# ROM_1_0.net
KiCad netlist of a schematic drawn in EAGLE
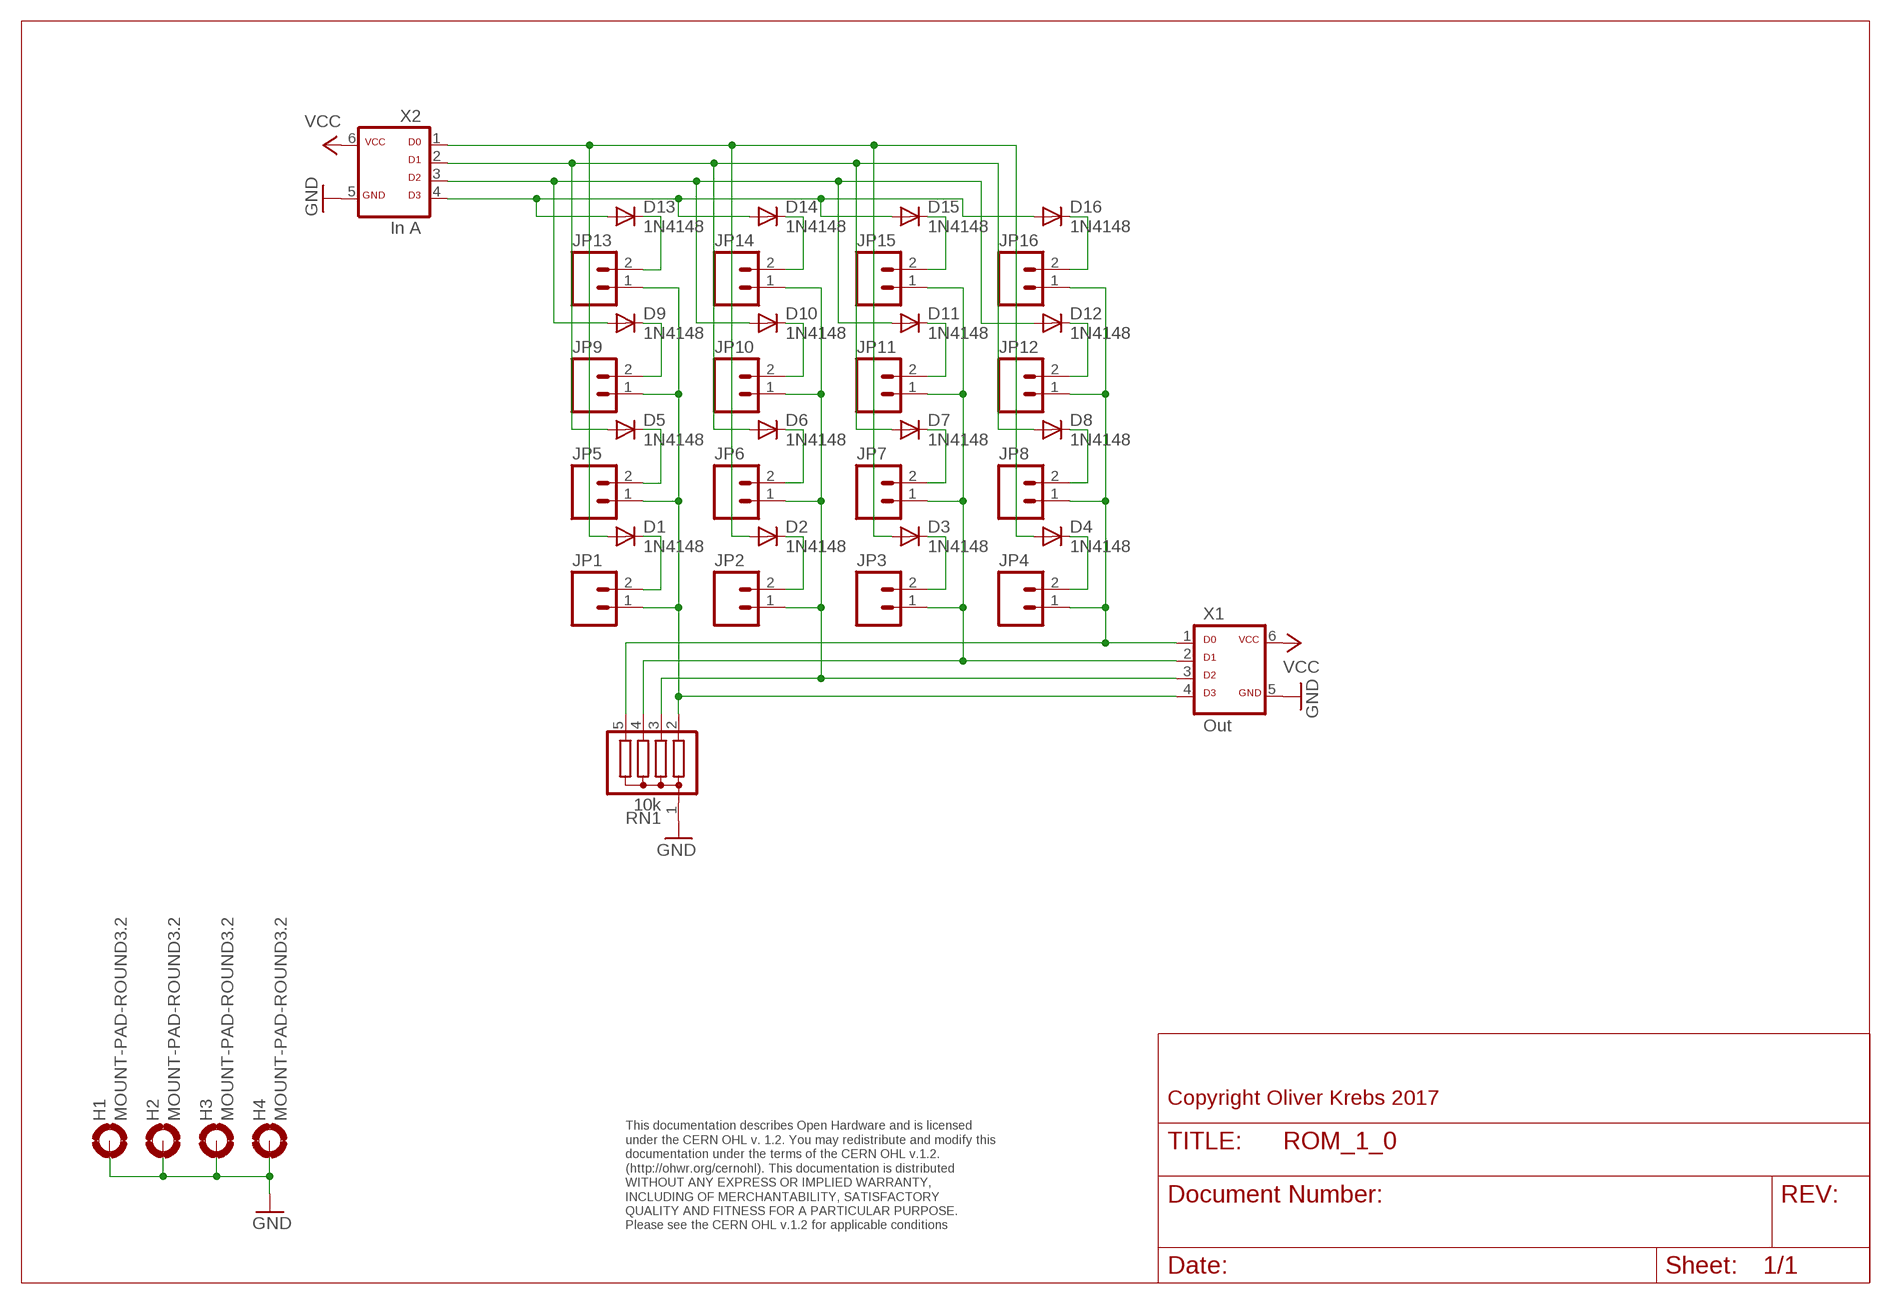
[diagram p0: schematic, sheet 1]

(export (version "E")
  (design (tool "Eeschema 10.0.6"))
  (components
    (comp (ref "D1")
      (value "1N4148")
      (footprint "eagle-import:DO35-7")
      (libsource (lib "eagle-import") (part "1N4148DO35-7"))
    )
    (comp (ref "D2")
      (value "1N4148")
      (footprint "eagle-import:DO35-7")
      (libsource (lib "eagle-import") (part "1N4148DO35-7"))
    )
    (comp (ref "D3")
      (value "1N4148")
      (footprint "eagle-import:DO35-7")
      (libsource (lib "eagle-import") (part "1N4148DO35-7"))
    )
    (comp (ref "D4")
      (value "1N4148")
      (footprint "eagle-import:DO35-7")
      (libsource (lib "eagle-import") (part "1N4148DO35-7"))
    )
    (comp (ref "D5")
      (value "1N4148")
      (footprint "eagle-import:DO35-7")
      (libsource (lib "eagle-import") (part "1N4148DO35-7"))
    )
    (comp (ref "D6")
      (value "1N4148")
      (footprint "eagle-import:DO35-7")
      (libsource (lib "eagle-import") (part "1N4148DO35-7"))
    )
    (comp (ref "D7")
      (value "1N4148")
      (footprint "eagle-import:DO35-7")
      (libsource (lib "eagle-import") (part "1N4148DO35-7"))
    )
    (comp (ref "D8")
      (value "1N4148")
      (footprint "eagle-import:DO35-7")
      (libsource (lib "eagle-import") (part "1N4148DO35-7"))
    )
    (comp (ref "D9")
      (value "1N4148")
      (footprint "eagle-import:DO35-7")
      (libsource (lib "eagle-import") (part "1N4148DO35-7"))
    )
    (comp (ref "D10")
      (value "1N4148")
      (footprint "eagle-import:DO35-7")
      (libsource (lib "eagle-import") (part "1N4148DO35-7"))
    )
    (comp (ref "D11")
      (value "1N4148")
      (footprint "eagle-import:DO35-7")
      (libsource (lib "eagle-import") (part "1N4148DO35-7"))
    )
    (comp (ref "D12")
      (value "1N4148")
      (footprint "eagle-import:DO35-7")
      (libsource (lib "eagle-import") (part "1N4148DO35-7"))
    )
    (comp (ref "D13")
      (value "1N4148")
      (footprint "eagle-import:DO35-7")
      (libsource (lib "eagle-import") (part "1N4148DO35-7"))
    )
    (comp (ref "D14")
      (value "1N4148")
      (footprint "eagle-import:DO35-7")
      (libsource (lib "eagle-import") (part "1N4148DO35-7"))
    )
    (comp (ref "D15")
      (value "1N4148")
      (footprint "eagle-import:DO35-7")
      (libsource (lib "eagle-import") (part "1N4148DO35-7"))
    )
    (comp (ref "D16")
      (value "1N4148")
      (footprint "eagle-import:DO35-7")
      (libsource (lib "eagle-import") (part "1N4148DO35-7"))
    )
    (comp (ref "H1")
      (value "MOUNT-PAD-ROUND3.2")
      (footprint "eagle-import:3,2-PAD")
      (libsource (lib "eagle-import") (part "MOUNT-PAD-ROUND3.2"))
    )
    (comp (ref "H2")
      (value "MOUNT-PAD-ROUND3.2")
      (footprint "eagle-import:3,2-PAD")
      (libsource (lib "eagle-import") (part "MOUNT-PAD-ROUND3.2"))
    )
    (comp (ref "H3")
      (value "MOUNT-PAD-ROUND3.2")
      (footprint "eagle-import:3,2-PAD")
      (libsource (lib "eagle-import") (part "MOUNT-PAD-ROUND3.2"))
    )
    (comp (ref "H4")
      (value "MOUNT-PAD-ROUND3.2")
      (footprint "eagle-import:3,2-PAD")
      (libsource (lib "eagle-import") (part "MOUNT-PAD-ROUND3.2"))
    )
    (comp (ref "JP1")
      (value "M02PTH")
      (footprint "eagle-import:1X02")
      (libsource (lib "eagle-import") (part "M02PTH"))
    )
    (comp (ref "JP2")
      (value "M02PTH")
      (footprint "eagle-import:1X02")
      (libsource (lib "eagle-import") (part "M02PTH"))
    )
    (comp (ref "JP3")
      (value "M02PTH")
      (footprint "eagle-import:1X02")
      (libsource (lib "eagle-import") (part "M02PTH"))
    )
    (comp (ref "JP4")
      (value "M02PTH")
      (footprint "eagle-import:1X02")
      (libsource (lib "eagle-import") (part "M02PTH"))
    )
    (comp (ref "JP5")
      (value "M02PTH")
      (footprint "eagle-import:1X02")
      (libsource (lib "eagle-import") (part "M02PTH"))
    )
    (comp (ref "JP6")
      (value "M02PTH")
      (footprint "eagle-import:1X02")
      (libsource (lib "eagle-import") (part "M02PTH"))
    )
    (comp (ref "JP7")
      (value "M02PTH")
      (footprint "eagle-import:1X02")
      (libsource (lib "eagle-import") (part "M02PTH"))
    )
    (comp (ref "JP8")
      (value "M02PTH")
      (footprint "eagle-import:1X02")
      (libsource (lib "eagle-import") (part "M02PTH"))
    )
    (comp (ref "JP9")
      (value "M02PTH")
      (footprint "eagle-import:1X02")
      (libsource (lib "eagle-import") (part "M02PTH"))
    )
    (comp (ref "JP10")
      (value "M02PTH")
      (footprint "eagle-import:1X02")
      (libsource (lib "eagle-import") (part "M02PTH"))
    )
    (comp (ref "JP11")
      (value "M02PTH")
      (footprint "eagle-import:1X02")
      (libsource (lib "eagle-import") (part "M02PTH"))
    )
    (comp (ref "JP12")
      (value "M02PTH")
      (footprint "eagle-import:1X02")
      (libsource (lib "eagle-import") (part "M02PTH"))
    )
    (comp (ref "JP13")
      (value "M02PTH")
      (footprint "eagle-import:1X02")
      (libsource (lib "eagle-import") (part "M02PTH"))
    )
    (comp (ref "JP14")
      (value "M02PTH")
      (footprint "eagle-import:1X02")
      (libsource (lib "eagle-import") (part "M02PTH"))
    )
    (comp (ref "JP15")
      (value "M02PTH")
      (footprint "eagle-import:1X02")
      (libsource (lib "eagle-import") (part "M02PTH"))
    )
    (comp (ref "JP16")
      (value "M02PTH")
      (footprint "eagle-import:1X02")
      (libsource (lib "eagle-import") (part "M02PTH"))
    )
    (comp (ref "RN1")
      (value "10k")
      (footprint "eagle-import:SIL5")
      (libsource (lib "eagle-import") (part "G04R"))
    )
    (comp (ref "X1")
      (value "Out")
      (footprint "eagle-import:ML-6")
      (libsource (lib "eagle-import") (part "ML6D"))
    )
    (comp (ref "X2")
      (value "In A")
      (footprint "eagle-import:ML-6")
      (libsource (lib "eagle-import") (part "ML6D"))
    )
  )
  (nets
    (net (code "1") (name "GND") (class "Default")
      (node (ref "H1") (pin "B3,2") (pinfunction "MOUNT_B3,2") (pintype "passive"))
      (node (ref "H2") (pin "B3,2") (pinfunction "MOUNT_B3,2") (pintype "passive"))
      (node (ref "H3") (pin "B3,2") (pinfunction "MOUNT_B3,2") (pintype "passive"))
      (node (ref "H4") (pin "B3,2") (pinfunction "MOUNT_B3,2") (pintype "passive"))
      (node (ref "RN1") (pin "1") (pinfunction "1_1") (pintype "passive"))
      (node (ref "X1") (pin "5") (pinfunction "5_5") (pintype "passive"))
      (node (ref "X2") (pin "5") (pinfunction "5_5") (pintype "passive"))
    )
    (net (code "2") (name "Net-(D1-PadA)") (class "Default")
      (node (ref "D1") (pin "A") (pinfunction "A_A") (pintype "passive"))
      (node (ref "D2") (pin "A") (pinfunction "A_A") (pintype "passive"))
      (node (ref "D3") (pin "A") (pinfunction "A_A") (pintype "passive"))
      (node (ref "D4") (pin "A") (pinfunction "A_A") (pintype "passive"))
      (node (ref "X2") (pin "1") (pinfunction "1_1") (pintype "passive"))
    )
    (net (code "3") (name "Net-(D1-PadC)") (class "Default")
      (node (ref "D1") (pin "C") (pinfunction "C_C") (pintype "passive"))
      (node (ref "JP1") (pin "2") (pinfunction "2_2") (pintype "passive"))
    )
    (net (code "4") (name "Net-(D2-PadC)") (class "Default")
      (node (ref "D2") (pin "C") (pinfunction "C_C") (pintype "passive"))
      (node (ref "JP2") (pin "2") (pinfunction "2_2") (pintype "passive"))
    )
    (net (code "5") (name "Net-(D3-PadC)") (class "Default")
      (node (ref "D3") (pin "C") (pinfunction "C_C") (pintype "passive"))
      (node (ref "JP3") (pin "2") (pinfunction "2_2") (pintype "passive"))
    )
    (net (code "6") (name "Net-(D4-PadC)") (class "Default")
      (node (ref "D4") (pin "C") (pinfunction "C_C") (pintype "passive"))
      (node (ref "JP4") (pin "2") (pinfunction "2_2") (pintype "passive"))
    )
    (net (code "7") (name "Net-(D5-PadA)") (class "Default")
      (node (ref "D5") (pin "A") (pinfunction "A_A") (pintype "passive"))
      (node (ref "D6") (pin "A") (pinfunction "A_A") (pintype "passive"))
      (node (ref "D7") (pin "A") (pinfunction "A_A") (pintype "passive"))
      (node (ref "D8") (pin "A") (pinfunction "A_A") (pintype "passive"))
      (node (ref "X2") (pin "2") (pinfunction "2_2") (pintype "passive"))
    )
    (net (code "8") (name "Net-(D5-PadC)") (class "Default")
      (node (ref "D5") (pin "C") (pinfunction "C_C") (pintype "passive"))
      (node (ref "JP5") (pin "2") (pinfunction "2_2") (pintype "passive"))
    )
    (net (code "9") (name "Net-(D6-PadC)") (class "Default")
      (node (ref "D6") (pin "C") (pinfunction "C_C") (pintype "passive"))
      (node (ref "JP6") (pin "2") (pinfunction "2_2") (pintype "passive"))
    )
    (net (code "10") (name "Net-(D7-PadC)") (class "Default")
      (node (ref "D7") (pin "C") (pinfunction "C_C") (pintype "passive"))
      (node (ref "JP7") (pin "2") (pinfunction "2_2") (pintype "passive"))
    )
    (net (code "11") (name "Net-(D8-PadC)") (class "Default")
      (node (ref "D8") (pin "C") (pinfunction "C_C") (pintype "passive"))
      (node (ref "JP8") (pin "2") (pinfunction "2_2") (pintype "passive"))
    )
    (net (code "12") (name "Net-(D9-PadC)") (class "Default")
      (node (ref "D9") (pin "C") (pinfunction "C_C") (pintype "passive"))
      (node (ref "JP9") (pin "2") (pinfunction "2_2") (pintype "passive"))
    )
    (net (code "13") (name "Net-(D10-PadA)") (class "Default")
      (node (ref "D10") (pin "A") (pinfunction "A_A") (pintype "passive"))
      (node (ref "D11") (pin "A") (pinfunction "A_A") (pintype "passive"))
      (node (ref "D12") (pin "A") (pinfunction "A_A") (pintype "passive"))
      (node (ref "D9") (pin "A") (pinfunction "A_A") (pintype "passive"))
      (node (ref "X2") (pin "3") (pinfunction "3_3") (pintype "passive"))
    )
    (net (code "14") (name "Net-(D10-PadC)") (class "Default")
      (node (ref "D10") (pin "C") (pinfunction "C_C") (pintype "passive"))
      (node (ref "JP10") (pin "2") (pinfunction "2_2") (pintype "passive"))
    )
    (net (code "15") (name "Net-(D11-PadC)") (class "Default")
      (node (ref "D11") (pin "C") (pinfunction "C_C") (pintype "passive"))
      (node (ref "JP11") (pin "2") (pinfunction "2_2") (pintype "passive"))
    )
    (net (code "16") (name "Net-(D12-PadC)") (class "Default")
      (node (ref "D12") (pin "C") (pinfunction "C_C") (pintype "passive"))
      (node (ref "JP12") (pin "2") (pinfunction "2_2") (pintype "passive"))
    )
    (net (code "17") (name "Net-(D13-PadA)") (class "Default")
      (node (ref "D13") (pin "A") (pinfunction "A_A") (pintype "passive"))
      (node (ref "D14") (pin "A") (pinfunction "A_A") (pintype "passive"))
      (node (ref "D15") (pin "A") (pinfunction "A_A") (pintype "passive"))
      (node (ref "D16") (pin "A") (pinfunction "A_A") (pintype "passive"))
      (node (ref "X2") (pin "4") (pinfunction "4_4") (pintype "passive"))
    )
    (net (code "18") (name "Net-(D13-PadC)") (class "Default")
      (node (ref "D13") (pin "C") (pinfunction "C_C") (pintype "passive"))
      (node (ref "JP13") (pin "2") (pinfunction "2_2") (pintype "passive"))
    )
    (net (code "19") (name "Net-(D14-PadC)") (class "Default")
      (node (ref "D14") (pin "C") (pinfunction "C_C") (pintype "passive"))
      (node (ref "JP14") (pin "2") (pinfunction "2_2") (pintype "passive"))
    )
    (net (code "20") (name "Net-(D15-PadC)") (class "Default")
      (node (ref "D15") (pin "C") (pinfunction "C_C") (pintype "passive"))
      (node (ref "JP15") (pin "2") (pinfunction "2_2") (pintype "passive"))
    )
    (net (code "21") (name "Net-(D16-PadC)") (class "Default")
      (node (ref "D16") (pin "C") (pinfunction "C_C") (pintype "passive"))
      (node (ref "JP16") (pin "2") (pinfunction "2_2") (pintype "passive"))
    )
    (net (code "22") (name "Net-(JP1-Pad1)") (class "Default")
      (node (ref "JP1") (pin "1") (pinfunction "1_1") (pintype "passive"))
      (node (ref "JP13") (pin "1") (pinfunction "1_1") (pintype "passive"))
      (node (ref "JP5") (pin "1") (pinfunction "1_1") (pintype "passive"))
      (node (ref "JP9") (pin "1") (pinfunction "1_1") (pintype "passive"))
      (node (ref "RN1") (pin "2") (pinfunction "2_2") (pintype "passive"))
      (node (ref "X1") (pin "4") (pinfunction "4_4") (pintype "passive"))
    )
    (net (code "23") (name "Net-(JP10-Pad1)") (class "Default")
      (node (ref "JP10") (pin "1") (pinfunction "1_1") (pintype "passive"))
      (node (ref "JP14") (pin "1") (pinfunction "1_1") (pintype "passive"))
      (node (ref "JP2") (pin "1") (pinfunction "1_1") (pintype "passive"))
      (node (ref "JP6") (pin "1") (pinfunction "1_1") (pintype "passive"))
      (node (ref "RN1") (pin "3") (pinfunction "3_3") (pintype "passive"))
      (node (ref "X1") (pin "3") (pinfunction "3_3") (pintype "passive"))
    )
    (net (code "24") (name "Net-(JP11-Pad1)") (class "Default")
      (node (ref "JP11") (pin "1") (pinfunction "1_1") (pintype "passive"))
      (node (ref "JP15") (pin "1") (pinfunction "1_1") (pintype "passive"))
      (node (ref "JP3") (pin "1") (pinfunction "1_1") (pintype "passive"))
      (node (ref "JP7") (pin "1") (pinfunction "1_1") (pintype "passive"))
      (node (ref "RN1") (pin "4") (pinfunction "4_4") (pintype "passive"))
      (node (ref "X1") (pin "2") (pinfunction "2_2") (pintype "passive"))
    )
    (net (code "25") (name "Net-(JP12-Pad1)") (class "Default")
      (node (ref "JP12") (pin "1") (pinfunction "1_1") (pintype "passive"))
      (node (ref "JP16") (pin "1") (pinfunction "1_1") (pintype "passive"))
      (node (ref "JP4") (pin "1") (pinfunction "1_1") (pintype "passive"))
      (node (ref "JP8") (pin "1") (pinfunction "1_1") (pintype "passive"))
      (node (ref "RN1") (pin "5") (pinfunction "5_5") (pintype "passive"))
      (node (ref "X1") (pin "1") (pinfunction "1_1") (pintype "passive"))
    )
    (net (code "26") (name "VCC") (class "Default")
      (node (ref "X1") (pin "6") (pinfunction "6_6") (pintype "passive"))
      (node (ref "X2") (pin "6") (pinfunction "6_6") (pintype "passive"))
    )
  )
)
